# mem.net
KiCad netlist of a schematic drawn in Altium Designer
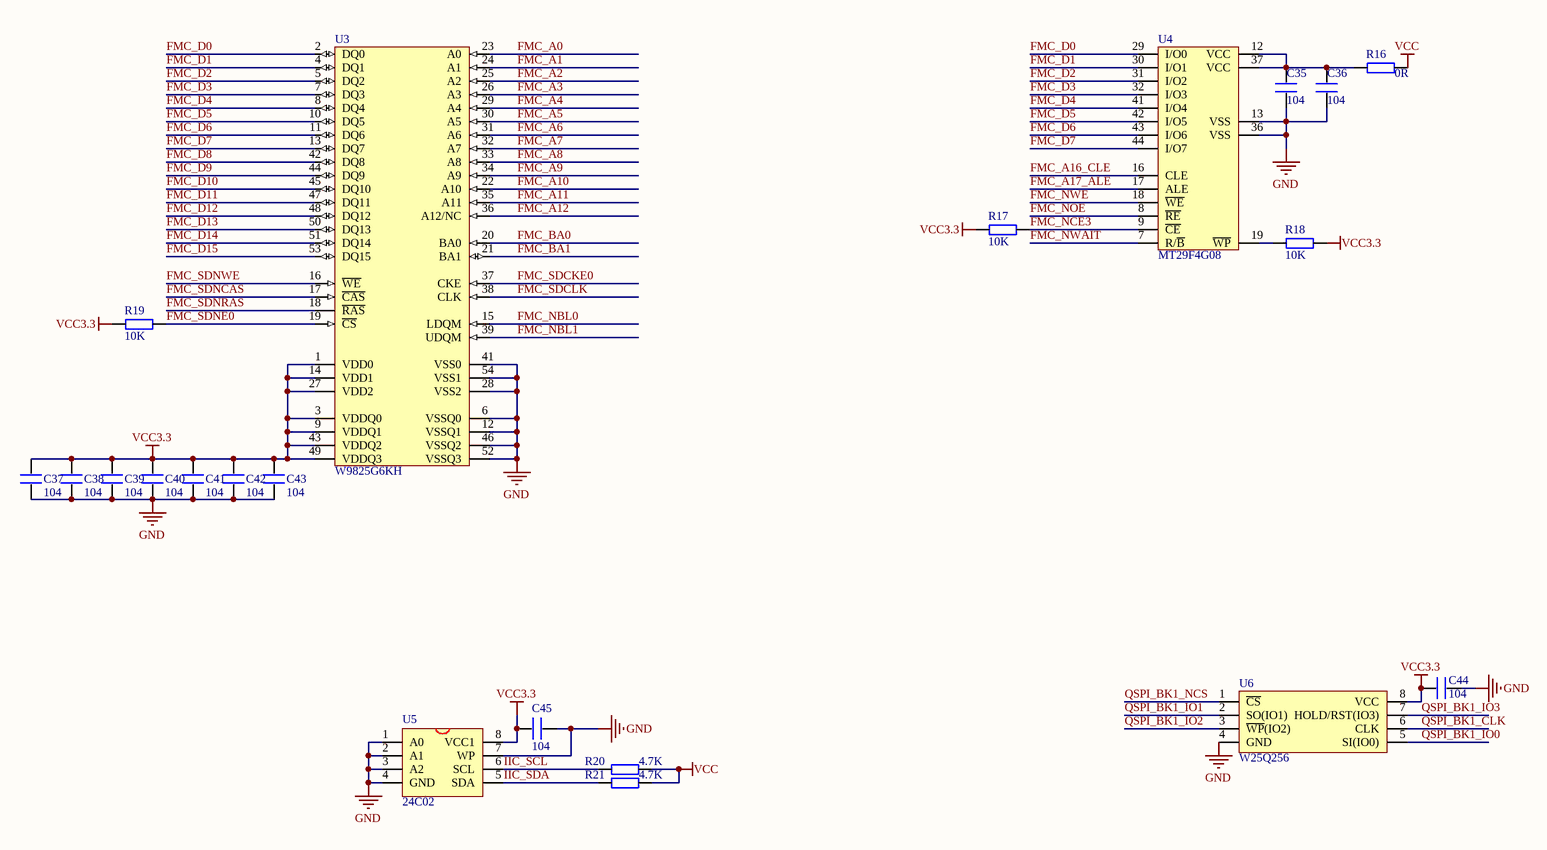
[diagram p0: mem.SchDoc]

(export (version "E")
  (design (tool "Eeschema 10.0.6"))
  (components
    (comp (ref "C35") (value "104") (footprint "0805") (libsource (lib "STM32F767核心板封装库") (part "C")))
    (comp (ref "C36") (value "104") (footprint "0805") (libsource (lib "STM32F767核心板封装库") (part "C")))
    (comp (ref "C37") (value "104") (footprint "0805") (libsource (lib "STM32F767核心板封装库") (part "C")))
    (comp (ref "C38") (value "104") (footprint "0805") (libsource (lib "STM32F767核心板封装库") (part "C")))
    (comp (ref "C39") (value "104") (footprint "0805") (libsource (lib "STM32F767核心板封装库") (part "C")))
    (comp (ref "C40") (value "104") (footprint "0805") (libsource (lib "STM32F767核心板封装库") (part "C")))
    (comp (ref "C41") (value "104") (footprint "0805") (libsource (lib "STM32F767核心板封装库") (part "C")))
    (comp (ref "C42") (value "104") (footprint "0805") (libsource (lib "STM32F767核心板封装库") (part "C")))
    (comp (ref "C43") (value "104") (footprint "0805") (libsource (lib "STM32F767核心板封装库") (part "C")))
    (comp (ref "C44") (value "104") (footprint "0805") (libsource (lib "STM32F767核心板封装库") (part "C")))
    (comp (ref "C45") (value "104") (footprint "0805") (libsource (lib "STM32F767核心板封装库") (part "C")))
    (comp (ref "R16") (value "0R") (footprint "0805") (libsource (lib "STM32F767核心板封装库") (part "R")))
    (comp (ref "R17") (value "10K") (footprint "0805") (libsource (lib "STM32F767核心板封装库") (part "R")))
    (comp (ref "R18") (value "10K") (footprint "0805") (libsource (lib "STM32F767核心板封装库") (part "R")))
    (comp (ref "R19") (value "10K") (footprint "0805") (libsource (lib "STM32F767核心板封装库") (part "R")))
    (comp (ref "R20") (value "4.7K") (footprint "0805") (libsource (lib "STM32F767核心板封装库") (part "R")))
    (comp (ref "R21") (value "4.7K") (footprint "0805") (libsource (lib "STM32F767核心板封装库") (part "R")))
    (comp (ref "U3")
      (value "W9825G6KH")
      (footprint "TSOP54")
      (description "32MB SDRAM")
      (libsource (lib "STM32F767核心板封装库") (part "IS42S16160B"))
    )
    (comp (ref "U4")
      (value "MT29F4G08")
      (footprint "TSOP48")
      (description "256MB NAND FLASH")
      (libsource (lib "STM32F767核心板封装库") (part "K9F2G08U0C"))
    )
    (comp (ref "U5")
      (value "24C02")
      (footprint "SOP-8")
      (description "EEPROM")
      (libsource (lib "STM32F767核心板封装库") (part "24C256"))
    )
    (comp (ref "U6")
      (value "W25Q256")
      (footprint "WSON8")
      (description "W25Q128")
      (libsource (lib "STM32F767核心板封装库") (part "W25Q128"))
    )
  )
  (nets
    (net (code "1") (name "/FMC_A0") (class "Default")
      (node (ref "U3") (pin "23") (pinfunction "A0_23") (pintype "input"))
    )
    (net (code "2") (name "/FMC_A1") (class "Default")
      (node (ref "U3") (pin "24") (pinfunction "A1_24") (pintype "input"))
    )
    (net (code "3") (name "/FMC_A2") (class "Default")
      (node (ref "U3") (pin "25") (pinfunction "A2_25") (pintype "input"))
    )
    (net (code "4") (name "/FMC_A3") (class "Default")
      (node (ref "U3") (pin "26") (pinfunction "A3_26") (pintype "input"))
    )
    (net (code "5") (name "/FMC_A4") (class "Default")
      (node (ref "U3") (pin "29") (pinfunction "A4_29") (pintype "input"))
    )
    (net (code "6") (name "/FMC_A5") (class "Default")
      (node (ref "U3") (pin "30") (pinfunction "A5_30") (pintype "input"))
    )
    (net (code "7") (name "/FMC_A6") (class "Default")
      (node (ref "U3") (pin "31") (pinfunction "A6_31") (pintype "input"))
    )
    (net (code "8") (name "/FMC_A7") (class "Default")
      (node (ref "U3") (pin "32") (pinfunction "A7_32") (pintype "input"))
    )
    (net (code "9") (name "/FMC_A8") (class "Default")
      (node (ref "U3") (pin "33") (pinfunction "A8_33") (pintype "input"))
    )
    (net (code "10") (name "/FMC_A9") (class "Default")
      (node (ref "U3") (pin "34") (pinfunction "A9_34") (pintype "input"))
    )
    (net (code "11") (name "/FMC_A10") (class "Default")
      (node (ref "U3") (pin "22") (pinfunction "A10_22") (pintype "input"))
    )
    (net (code "12") (name "/FMC_A11") (class "Default")
      (node (ref "U3") (pin "35") (pinfunction "A11_35") (pintype "input"))
    )
    (net (code "13") (name "/FMC_A12") (class "Default")
      (node (ref "U3") (pin "36") (pinfunction "A12/NC_36") (pintype "input"))
    )
    (net (code "14") (name "/FMC_A16_CLE") (class "Default")
      (node (ref "U4") (pin "16") (pinfunction "CLE_16") (pintype "passive"))
    )
    (net (code "15") (name "/FMC_A17_ALE") (class "Default")
      (node (ref "U4") (pin "17") (pinfunction "ALE_17") (pintype "passive"))
    )
    (net (code "16") (name "/FMC_BA0") (class "Default")
      (node (ref "U3") (pin "20") (pinfunction "BA0_20") (pintype "input"))
    )
    (net (code "17") (name "/FMC_BA1") (class "Default")
      (node (ref "U3") (pin "21") (pinfunction "BA1_21") (pintype "bidirectional"))
    )
    (net (code "18") (name "/FMC_D0") (class "Default")
      (node (ref "U3") (pin "2") (pinfunction "DQ0_2") (pintype "bidirectional"))
      (node (ref "U4") (pin "29") (pinfunction "I/O0_29") (pintype "passive"))
    )
    (net (code "19") (name "/FMC_D1") (class "Default")
      (node (ref "U3") (pin "4") (pinfunction "DQ1_4") (pintype "bidirectional"))
      (node (ref "U4") (pin "30") (pinfunction "I/O1_30") (pintype "passive"))
    )
    (net (code "20") (name "/FMC_D2") (class "Default")
      (node (ref "U3") (pin "5") (pinfunction "DQ2_5") (pintype "bidirectional"))
      (node (ref "U4") (pin "31") (pinfunction "I/O2_31") (pintype "passive"))
    )
    (net (code "21") (name "/FMC_D3") (class "Default")
      (node (ref "U3") (pin "7") (pinfunction "DQ3_7") (pintype "bidirectional"))
      (node (ref "U4") (pin "32") (pinfunction "I/O3_32") (pintype "passive"))
    )
    (net (code "22") (name "/FMC_D4") (class "Default")
      (node (ref "U3") (pin "8") (pinfunction "DQ4_8") (pintype "bidirectional"))
      (node (ref "U4") (pin "41") (pinfunction "I/O4_41") (pintype "passive"))
    )
    (net (code "23") (name "/FMC_D5") (class "Default")
      (node (ref "U3") (pin "10") (pinfunction "DQ5_10") (pintype "bidirectional"))
      (node (ref "U4") (pin "42") (pinfunction "I/O5_42") (pintype "passive"))
    )
    (net (code "24") (name "/FMC_D6") (class "Default")
      (node (ref "U3") (pin "11") (pinfunction "DQ6_11") (pintype "bidirectional"))
      (node (ref "U4") (pin "43") (pinfunction "I/O6_43") (pintype "passive"))
    )
    (net (code "25") (name "/FMC_D7") (class "Default")
      (node (ref "U3") (pin "13") (pinfunction "DQ7_13") (pintype "bidirectional"))
      (node (ref "U4") (pin "44") (pinfunction "I/O7_44") (pintype "passive"))
    )
    (net (code "26") (name "/FMC_D8") (class "Default")
      (node (ref "U3") (pin "42") (pinfunction "DQ8_42") (pintype "bidirectional"))
    )
    (net (code "27") (name "/FMC_D9") (class "Default")
      (node (ref "U3") (pin "44") (pinfunction "DQ9_44") (pintype "bidirectional"))
    )
    (net (code "28") (name "/FMC_D10") (class "Default")
      (node (ref "U3") (pin "45") (pinfunction "DQ10_45") (pintype "bidirectional"))
    )
    (net (code "29") (name "/FMC_D11") (class "Default")
      (node (ref "U3") (pin "47") (pinfunction "DQ11_47") (pintype "bidirectional"))
    )
    (net (code "30") (name "/FMC_D12") (class "Default")
      (node (ref "U3") (pin "48") (pinfunction "DQ12_48") (pintype "bidirectional"))
    )
    (net (code "31") (name "/FMC_D13") (class "Default")
      (node (ref "U3") (pin "50") (pinfunction "DQ13_50") (pintype "bidirectional"))
    )
    (net (code "32") (name "/FMC_D14") (class "Default")
      (node (ref "U3") (pin "51") (pinfunction "DQ14_51") (pintype "bidirectional"))
    )
    (net (code "33") (name "/FMC_D15") (class "Default")
      (node (ref "U3") (pin "53") (pinfunction "DQ15_53") (pintype "bidirectional"))
    )
    (net (code "34") (name "/FMC_NBL0") (class "Default")
      (node (ref "U3") (pin "15") (pinfunction "LDQM_15") (pintype "input"))
    )
    (net (code "35") (name "/FMC_NBL1") (class "Default")
      (node (ref "U3") (pin "39") (pinfunction "UDQM_39") (pintype "input"))
    )
    (net (code "36") (name "/FMC_NCE3") (class "Default")
      (node (ref "R17") (pin "2") (pintype "passive"))
      (node (ref "U4") (pin "9") (pinfunction "~{CE}_9") (pintype "passive"))
    )
    (net (code "37") (name "/FMC_NOE") (class "Default")
      (node (ref "U4") (pin "8") (pinfunction "~{RE}_8") (pintype "passive"))
    )
    (net (code "38") (name "/FMC_NWAIT") (class "Default")
      (node (ref "U4") (pin "7") (pinfunction "R/~{B}_7") (pintype "passive"))
    )
    (net (code "39") (name "/FMC_NWE") (class "Default")
      (node (ref "U4") (pin "18") (pinfunction "~{WE}_18") (pintype "passive"))
    )
    (net (code "40") (name "/FMC_SDCKE0") (class "Default")
      (node (ref "U3") (pin "37") (pinfunction "CKE_37") (pintype "input"))
    )
    (net (code "41") (name "/FMC_SDCLK") (class "Default")
      (node (ref "U3") (pin "38") (pinfunction "CLK_38") (pintype "input"))
    )
    (net (code "42") (name "/FMC_SDNCAS") (class "Default")
      (node (ref "U3") (pin "17") (pinfunction "~{CAS}_17") (pintype "input"))
    )
    (net (code "43") (name "/FMC_SDNE0") (class "Default")
      (node (ref "R19") (pin "2") (pintype "passive"))
      (node (ref "U3") (pin "19") (pinfunction "~{CS}_19") (pintype "input"))
    )
    (net (code "44") (name "/FMC_SDNRAS") (class "Default")
      (node (ref "U3") (pin "18") (pinfunction "~{RAS}_18") (pintype "passive"))
    )
    (net (code "45") (name "/FMC_SDNWE") (class "Default")
      (node (ref "U3") (pin "16") (pinfunction "~{WE}_16") (pintype "input"))
    )
    (net (code "46") (name "/IIC_SCL") (class "Default")
      (node (ref "R20") (pin "1") (pintype "passive"))
      (node (ref "U5") (pin "6") (pinfunction "SCL_6") (pintype "passive"))
    )
    (net (code "47") (name "/IIC_SDA") (class "Default")
      (node (ref "R21") (pin "1") (pintype "passive"))
      (node (ref "U5") (pin "5") (pinfunction "SDA_5") (pintype "passive"))
    )
    (net (code "48") (name "/QSPI_BK1_CLK") (class "Default")
      (node (ref "U6") (pin "6") (pinfunction "CLK_6") (pintype "passive"))
    )
    (net (code "49") (name "/QSPI_BK1_IO0") (class "Default")
      (node (ref "U6") (pin "5") (pinfunction "SI(IO0)_5") (pintype "power_in"))
    )
    (net (code "50") (name "/QSPI_BK1_IO1") (class "Default")
      (node (ref "U6") (pin "2") (pinfunction "SO(IO1)_2") (pintype "passive"))
    )
    (net (code "51") (name "/QSPI_BK1_IO2") (class "Default")
      (node (ref "U6") (pin "3") (pinfunction "~{WP}(IO2)_3") (pintype "passive"))
    )
    (net (code "52") (name "/QSPI_BK1_IO3") (class "Default")
      (node (ref "U6") (pin "7") (pinfunction "HOLD/RST(IO3)_7") (pintype "power_in"))
    )
    (net (code "53") (name "/QSPI_BK1_NCS") (class "Default")
      (node (ref "U6") (pin "1") (pinfunction "~{CS}_1") (pintype "passive"))
    )
    (net (code "54") (name "GND") (class "Default")
      (node (ref "C35") (pin "1") (pintype "passive"))
      (node (ref "C36") (pin "1") (pintype "passive"))
      (node (ref "C37") (pin "1") (pintype "passive"))
      (node (ref "C38") (pin "1") (pintype "passive"))
      (node (ref "C39") (pin "1") (pintype "passive"))
      (node (ref "C40") (pin "1") (pintype "passive"))
      (node (ref "C41") (pin "1") (pintype "passive"))
      (node (ref "C42") (pin "1") (pintype "passive"))
      (node (ref "C43") (pin "1") (pintype "passive"))
      (node (ref "C44") (pin "2") (pintype "passive"))
      (node (ref "C45") (pin "2") (pintype "passive"))
      (node (ref "U3") (pin "12") (pinfunction "VSSQ1_12") (pintype "power_in"))
      (node (ref "U3") (pin "28") (pinfunction "VSS2_28") (pintype "power_in"))
      (node (ref "U3") (pin "41") (pinfunction "VSS0_41") (pintype "power_in"))
      (node (ref "U3") (pin "46") (pinfunction "VSSQ2_46") (pintype "power_in"))
      (node (ref "U3") (pin "52") (pinfunction "VSSQ3_52") (pintype "power_in"))
      (node (ref "U3") (pin "54") (pinfunction "VSS1_54") (pintype "power_in"))
      (node (ref "U3") (pin "6") (pinfunction "VSSQ0_6") (pintype "power_in"))
      (node (ref "U4") (pin "13") (pinfunction "VSS_13") (pintype "passive"))
      (node (ref "U4") (pin "36") (pinfunction "VSS_36") (pintype "passive"))
      (node (ref "U5") (pin "1") (pinfunction "A0_1") (pintype "passive"))
      (node (ref "U5") (pin "2") (pinfunction "A1_2") (pintype "passive"))
      (node (ref "U5") (pin "3") (pinfunction "A2_3") (pintype "passive"))
      (node (ref "U5") (pin "4") (pinfunction "GND_4") (pintype "passive"))
      (node (ref "U5") (pin "7") (pinfunction "WP_7") (pintype "passive"))
      (node (ref "U6") (pin "4") (pinfunction "GND_4") (pintype "passive"))
    )
    (net (code "55") (name "Net-(C35-Pad2)") (class "Default")
      (node (ref "C35") (pin "2") (pintype "passive"))
      (node (ref "C36") (pin "2") (pintype "passive"))
      (node (ref "R16") (pin "1") (pintype "passive"))
      (node (ref "U4") (pin "12") (pinfunction "VCC_12") (pintype "passive"))
      (node (ref "U4") (pin "37") (pinfunction "VCC_37") (pintype "passive"))
    )
    (net (code "56") (name "Net-(U4-~{WP})") (class "Default")
      (node (ref "R18") (pin "1") (pintype "passive"))
      (node (ref "U4") (pin "19") (pinfunction "~{WP}_19") (pintype "passive"))
    )
    (net (code "57") (name "VCC") (class "Default")
      (node (ref "R16") (pin "2") (pintype "passive"))
      (node (ref "R20") (pin "2") (pintype "passive"))
      (node (ref "R21") (pin "2") (pintype "passive"))
    )
    (net (code "58") (name "VCC3.3") (class "Default")
      (node (ref "C37") (pin "2") (pintype "passive"))
      (node (ref "C38") (pin "2") (pintype "passive"))
      (node (ref "C39") (pin "2") (pintype "passive"))
      (node (ref "C40") (pin "2") (pintype "passive"))
      (node (ref "C41") (pin "2") (pintype "passive"))
      (node (ref "C42") (pin "2") (pintype "passive"))
      (node (ref "C43") (pin "2") (pintype "passive"))
      (node (ref "C44") (pin "1") (pintype "passive"))
      (node (ref "C45") (pin "1") (pintype "passive"))
      (node (ref "R17") (pin "1") (pintype "passive"))
      (node (ref "R18") (pin "2") (pintype "passive"))
      (node (ref "R19") (pin "1") (pintype "passive"))
      (node (ref "U3") (pin "1") (pinfunction "VDD0_1") (pintype "power_in"))
      (node (ref "U3") (pin "14") (pinfunction "VDD1_14") (pintype "power_in"))
      (node (ref "U3") (pin "27") (pinfunction "VDD2_27") (pintype "power_in"))
      (node (ref "U3") (pin "3") (pinfunction "VDDQ0_3") (pintype "power_in"))
      (node (ref "U3") (pin "43") (pinfunction "VDDQ2_43") (pintype "power_in"))
      (node (ref "U3") (pin "49") (pinfunction "VDDQ3_49") (pintype "power_in"))
      (node (ref "U3") (pin "9") (pinfunction "VDDQ1_9") (pintype "power_in"))
      (node (ref "U5") (pin "8") (pinfunction "VCC1_8") (pintype "passive"))
      (node (ref "U6") (pin "8") (pinfunction "VCC_8") (pintype "passive"))
    )
  )
)
